# EEZ_DIB_PREL6_r1B3.net
KiCad netlist of a schematic drawn in EAGLE
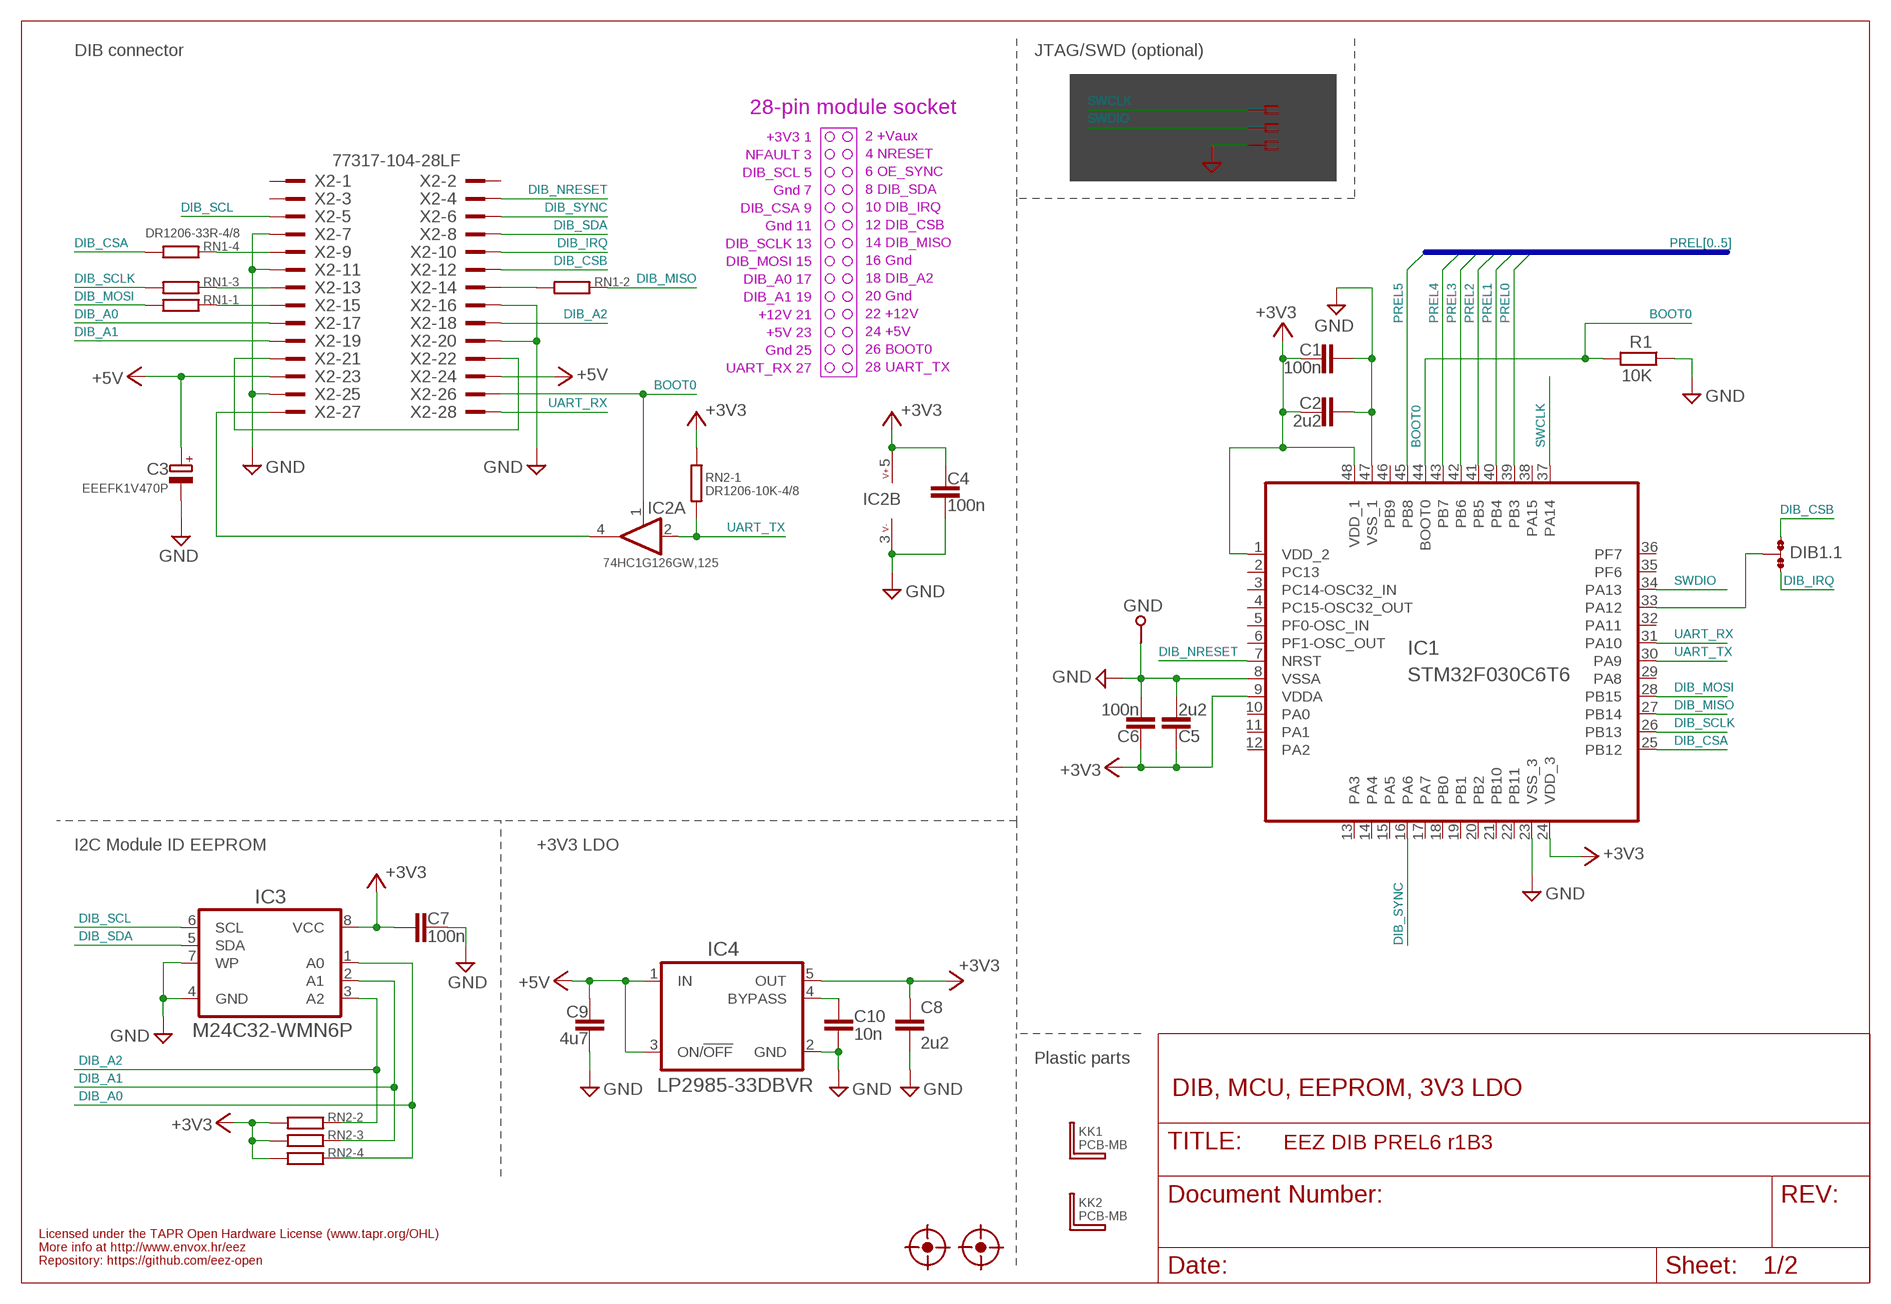
[diagram p0: schematic, sheet 1]
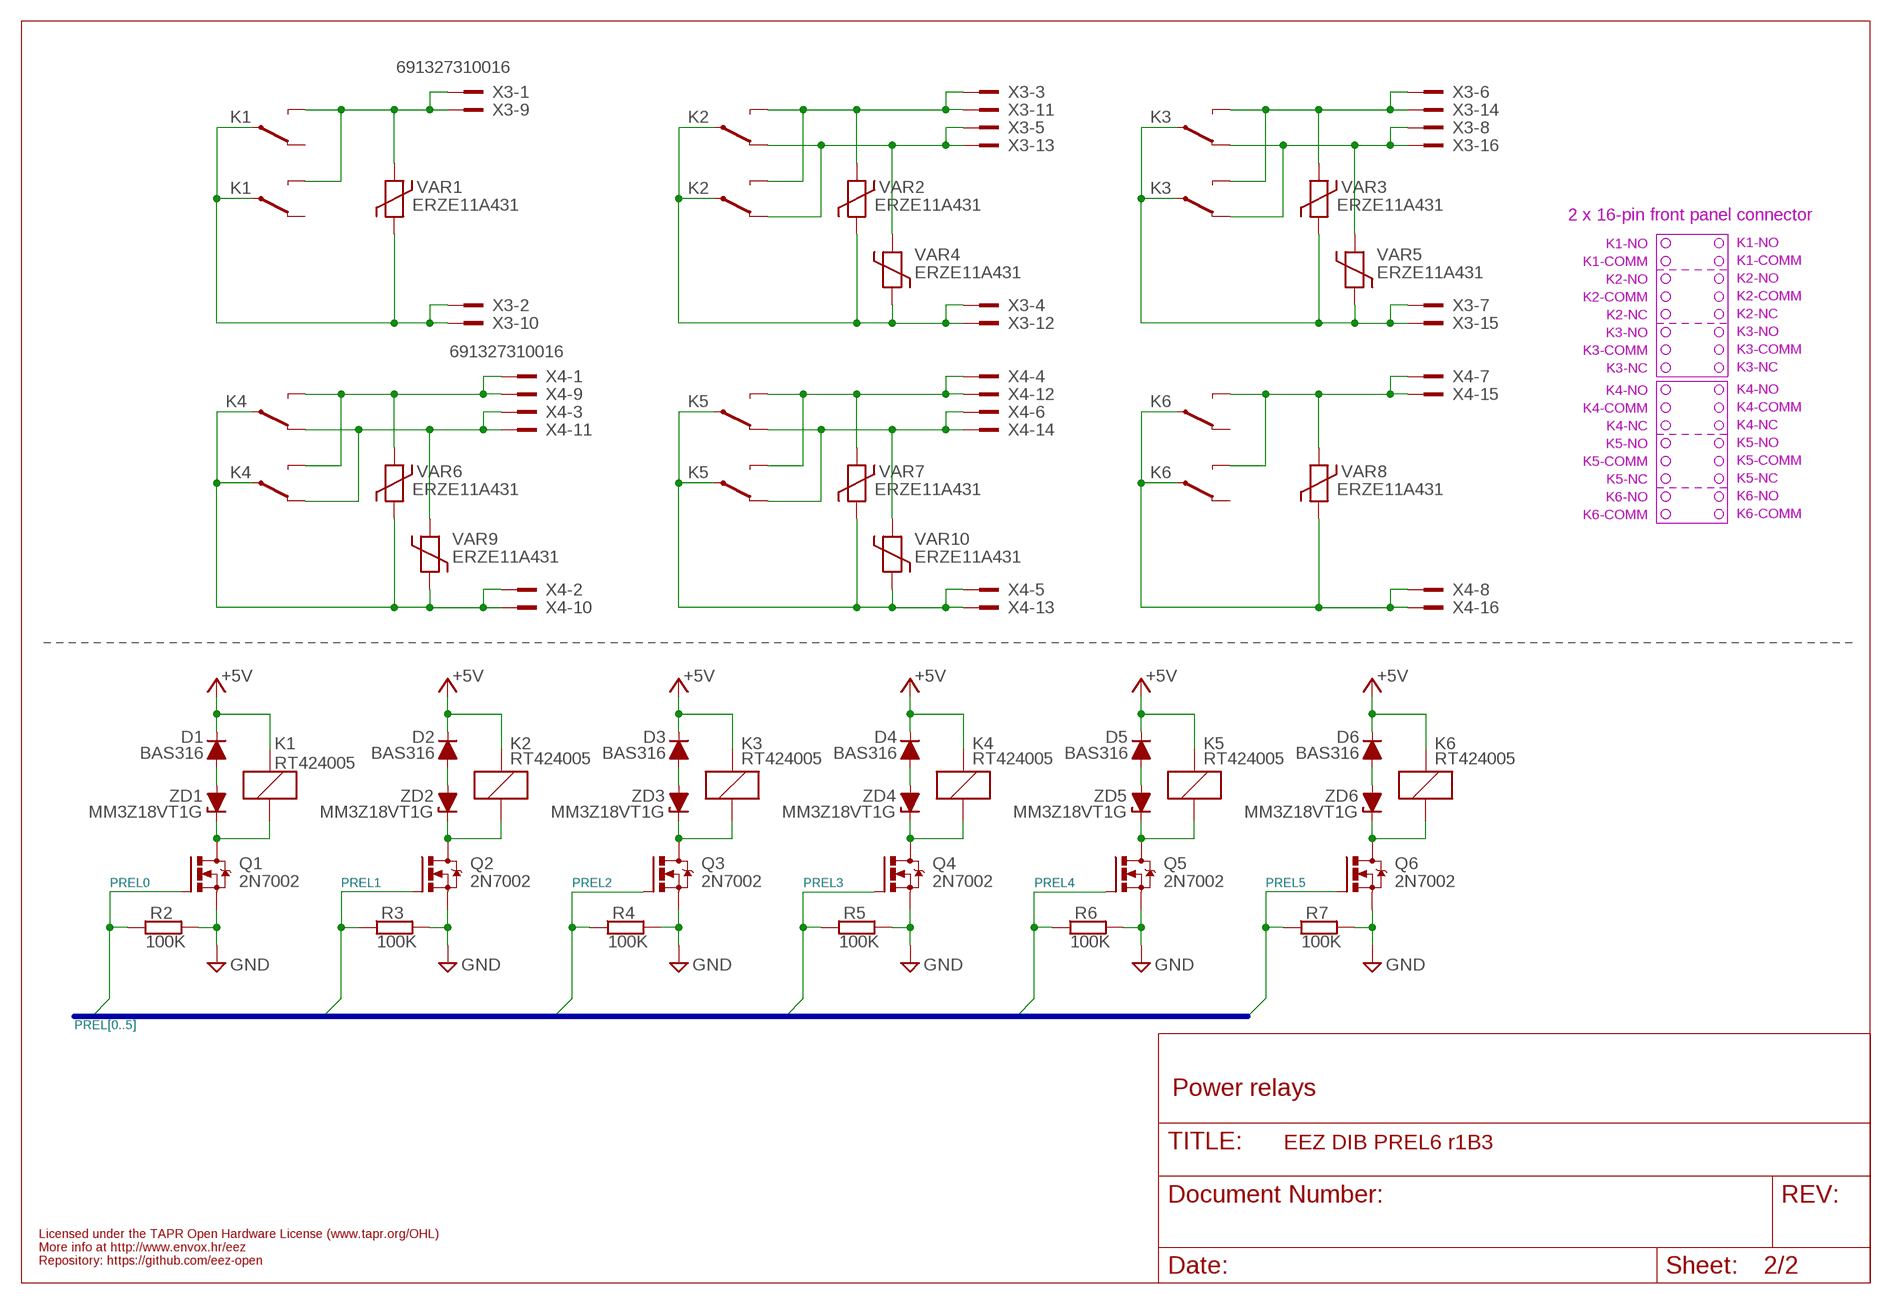
[diagram p1: schematic, sheet 2]

(export (version "E")
  (design (tool "Eeschema 10.0.6"))
  (components
    (comp (ref "D1")
      (value "BAS316")
      (footprint "eagle-import:SOD323-R")
      (libsource (lib "eagle-import") (part "DIODESOD323R"))
    )
    (comp (ref "D2")
      (value "BAS316")
      (footprint "eagle-import:SOD323-R")
      (libsource (lib "eagle-import") (part "DIODESOD323R"))
    )
    (comp (ref "D3")
      (value "BAS316")
      (footprint "eagle-import:SOD323-R")
      (libsource (lib "eagle-import") (part "DIODESOD323R"))
    )
    (comp (ref "D4")
      (value "BAS316")
      (footprint "eagle-import:SOD323-R")
      (libsource (lib "eagle-import") (part "DIODESOD323R"))
    )
    (comp (ref "D5")
      (value "BAS316")
      (footprint "eagle-import:SOD323-R")
      (libsource (lib "eagle-import") (part "DIODESOD323R"))
    )
    (comp (ref "D6")
      (value "BAS316")
      (footprint "eagle-import:SOD323-R")
      (libsource (lib "eagle-import") (part "DIODESOD323R"))
    )
    (comp (ref "K1")
      (value "RT424005")
      (footprint "eagle-import:RT-C_016A5_ROUND")
      (libsource (lib "eagle-import") (part "RELAY_RT314012-2"))
    )
    (comp (ref "K2")
      (value "RT424005")
      (footprint "eagle-import:RT-C_016A5_ROUND")
      (libsource (lib "eagle-import") (part "RELAY_RT314012-2"))
    )
    (comp (ref "K3")
      (value "RT424005")
      (footprint "eagle-import:RT-C_016A5_ROUND")
      (libsource (lib "eagle-import") (part "RELAY_RT314012-2"))
    )
    (comp (ref "K4")
      (value "RT424005")
      (footprint "eagle-import:RT-C_016A5_ROUND")
      (libsource (lib "eagle-import") (part "RELAY_RT314012-2"))
    )
    (comp (ref "K5")
      (value "RT424005")
      (footprint "eagle-import:RT-C_016A5_ROUND")
      (libsource (lib "eagle-import") (part "RELAY_RT314012-2"))
    )
    (comp (ref "K6")
      (value "RT424005")
      (footprint "eagle-import:RT-C_016A5_ROUND")
      (libsource (lib "eagle-import") (part "RELAY_RT314012-2"))
    )
    (comp (ref "Q1")
      (value "2N7002")
      (footprint "eagle-import:SOT103P240X110-3N")
      (fields
        (field (name "MPN") "2N7002-7-F")
        (field (name "MPN_1") "2N7002-7-F")
        (field (name "OC_FARNELL") "1713823")
        (field (name "OC_NEWARK") "25R5679")
        (field (name "PACKAGE") "SOT-23-3")
        (field (name "SUPPLIER") "DIODES INC.")
      )
      (libsource (lib "eagle-import") (part "2N7002"))
    )
    (comp (ref "Q2")
      (value "2N7002")
      (footprint "eagle-import:SOT103P240X110-3N")
      (fields
        (field (name "MPN") "2N7002-7-F")
        (field (name "MPN_1") "2N7002-7-F")
        (field (name "OC_FARNELL") "1713823")
        (field (name "OC_NEWARK") "25R5679")
        (field (name "PACKAGE") "SOT-23-3")
        (field (name "SUPPLIER") "DIODES INC.")
      )
      (libsource (lib "eagle-import") (part "2N7002"))
    )
    (comp (ref "Q3")
      (value "2N7002")
      (footprint "eagle-import:SOT103P240X110-3N")
      (fields
        (field (name "MPN") "2N7002-7-F")
        (field (name "MPN_1") "2N7002-7-F")
        (field (name "OC_FARNELL") "1713823")
        (field (name "OC_NEWARK") "25R5679")
        (field (name "PACKAGE") "SOT-23-3")
        (field (name "SUPPLIER") "DIODES INC.")
      )
      (libsource (lib "eagle-import") (part "2N7002"))
    )
    (comp (ref "Q4")
      (value "2N7002")
      (footprint "eagle-import:SOT103P240X110-3N")
      (fields
        (field (name "MPN") "2N7002-7-F")
        (field (name "MPN_1") "2N7002-7-F")
        (field (name "OC_FARNELL") "1713823")
        (field (name "OC_NEWARK") "25R5679")
        (field (name "PACKAGE") "SOT-23-3")
        (field (name "SUPPLIER") "DIODES INC.")
      )
      (libsource (lib "eagle-import") (part "2N7002"))
    )
    (comp (ref "Q5")
      (value "2N7002")
      (footprint "eagle-import:SOT103P240X110-3N")
      (fields
        (field (name "MPN") "2N7002-7-F")
        (field (name "MPN_1") "2N7002-7-F")
        (field (name "OC_FARNELL") "1713823")
        (field (name "OC_NEWARK") "25R5679")
        (field (name "PACKAGE") "SOT-23-3")
        (field (name "SUPPLIER") "DIODES INC.")
      )
      (libsource (lib "eagle-import") (part "2N7002"))
    )
    (comp (ref "Q6")
      (value "2N7002")
      (footprint "eagle-import:SOT103P240X110-3N")
      (fields
        (field (name "MPN") "2N7002-7-F")
        (field (name "MPN_1") "2N7002-7-F")
        (field (name "OC_FARNELL") "1713823")
        (field (name "OC_NEWARK") "25R5679")
        (field (name "PACKAGE") "SOT-23-3")
        (field (name "SUPPLIER") "DIODES INC.")
      )
      (libsource (lib "eagle-import") (part "2N7002"))
    )
    (comp (ref "R2")
      (value "100K")
      (footprint "eagle-import:R0805")
      (libsource (lib "eagle-import") (part "R-EU_R0805"))
    )
    (comp (ref "R3")
      (value "100K")
      (footprint "eagle-import:R0805")
      (libsource (lib "eagle-import") (part "R-EU_R0805"))
    )
    (comp (ref "R4")
      (value "100K")
      (footprint "eagle-import:R0805")
      (libsource (lib "eagle-import") (part "R-EU_R0805"))
    )
    (comp (ref "R5")
      (value "100K")
      (footprint "eagle-import:R0805")
      (libsource (lib "eagle-import") (part "R-EU_R0805"))
    )
    (comp (ref "R6")
      (value "100K")
      (footprint "eagle-import:R0805")
      (libsource (lib "eagle-import") (part "R-EU_R0805"))
    )
    (comp (ref "R7")
      (value "100K")
      (footprint "eagle-import:R0805")
      (libsource (lib "eagle-import") (part "R-EU_R0805"))
    )
    (comp (ref "VAR1")
      (value "ERZE11A431")
      (footprint "eagle-import:VARISTOR_13MM")
      (libsource (lib "eagle-import") (part "VARISTOR-13"))
    )
    (comp (ref "VAR2")
      (value "ERZE11A431")
      (footprint "eagle-import:VARISTOR_13MM")
      (libsource (lib "eagle-import") (part "VARISTOR-13"))
    )
    (comp (ref "VAR3")
      (value "ERZE11A431")
      (footprint "eagle-import:VARISTOR_13MM")
      (libsource (lib "eagle-import") (part "VARISTOR-13"))
    )
    (comp (ref "VAR4")
      (value "ERZE11A431")
      (footprint "eagle-import:VARISTOR_13MM")
      (libsource (lib "eagle-import") (part "VARISTOR-13"))
    )
    (comp (ref "VAR5")
      (value "ERZE11A431")
      (footprint "eagle-import:VARISTOR_13MM")
      (libsource (lib "eagle-import") (part "VARISTOR-13"))
    )
    (comp (ref "VAR6")
      (value "ERZE11A431")
      (footprint "eagle-import:VARISTOR_13MM")
      (libsource (lib "eagle-import") (part "VARISTOR-13"))
    )
    (comp (ref "VAR7")
      (value "ERZE11A431")
      (footprint "eagle-import:VARISTOR_13MM")
      (libsource (lib "eagle-import") (part "VARISTOR-13"))
    )
    (comp (ref "VAR8")
      (value "ERZE11A431")
      (footprint "eagle-import:VARISTOR_13MM")
      (libsource (lib "eagle-import") (part "VARISTOR-13"))
    )
    (comp (ref "VAR9")
      (value "ERZE11A431")
      (footprint "eagle-import:VARISTOR_13MM")
      (libsource (lib "eagle-import") (part "VARISTOR-13"))
    )
    (comp (ref "VAR10")
      (value "ERZE11A431")
      (footprint "eagle-import:VARISTOR_13MM")
      (libsource (lib "eagle-import") (part "VARISTOR-13"))
    )
    (comp (ref "X3")
      (value "691327310016")
      (footprint "eagle-import:691327310016")
      (libsource (lib "eagle-import") (part "691327310016"))
    )
    (comp (ref "X4")
      (value "691327310016")
      (footprint "eagle-import:691327310016")
      (libsource (lib "eagle-import") (part "691327310016"))
    )
    (comp (ref "ZD1")
      (value "MM3Z18VT1G")
      (footprint "eagle-import:SOD323-R")
      (libsource (lib "eagle-import") (part "ZENER-DIODESOD323R"))
    )
    (comp (ref "ZD2")
      (value "MM3Z18VT1G")
      (footprint "eagle-import:SOD323-R")
      (libsource (lib "eagle-import") (part "ZENER-DIODESOD323R"))
    )
    (comp (ref "ZD3")
      (value "MM3Z18VT1G")
      (footprint "eagle-import:SOD323-R")
      (libsource (lib "eagle-import") (part "ZENER-DIODESOD323R"))
    )
    (comp (ref "ZD4")
      (value "MM3Z18VT1G")
      (footprint "eagle-import:SOD323-R")
      (libsource (lib "eagle-import") (part "ZENER-DIODESOD323R"))
    )
    (comp (ref "ZD5")
      (value "MM3Z18VT1G")
      (footprint "eagle-import:SOD323-R")
      (libsource (lib "eagle-import") (part "ZENER-DIODESOD323R"))
    )
    (comp (ref "ZD6")
      (value "MM3Z18VT1G")
      (footprint "eagle-import:SOD323-R")
      (libsource (lib "eagle-import") (part "ZENER-DIODESOD323R"))
    )
    (comp (ref "C1")
      (value "100n")
      (footprint "eagle-import:C0603")
      (libsource (lib "eagle-import") (part "C-EUC0603"))
    )
    (comp (ref "C2")
      (value "2u2")
      (footprint "eagle-import:C0805")
      (libsource (lib "eagle-import") (part "C-EUC0805"))
    )
    (comp (ref "C3")
      (value "EEEFK1V470P")
      (footprint "eagle-import:CAPAE660X610N")
      (libsource (lib "eagle-import") (part "ECAPPANASONIC_H"))
    )
    (comp (ref "C4")
      (value "100n")
      (footprint "eagle-import:C0603")
      (libsource (lib "eagle-import") (part "C-EUC0603"))
    )
    (comp (ref "C5")
      (value "2u2")
      (footprint "eagle-import:C0805")
      (libsource (lib "eagle-import") (part "C-EUC0805"))
    )
    (comp (ref "C6")
      (value "100n")
      (footprint "eagle-import:C0603")
      (libsource (lib "eagle-import") (part "C-EUC0603"))
    )
    (comp (ref "C7")
      (value "100n")
      (footprint "eagle-import:C0603")
      (libsource (lib "eagle-import") (part "C-EUC0603"))
    )
    (comp (ref "C8")
      (value "2u2")
      (footprint "eagle-import:C0805")
      (libsource (lib "eagle-import") (part "C-EUC0805"))
    )
    (comp (ref "C9")
      (value "4u7")
      (footprint "eagle-import:C0805")
      (libsource (lib "eagle-import") (part "C-EUC0805"))
    )
    (comp (ref "C10")
      (value "10n")
      (footprint "eagle-import:C0805")
      (libsource (lib "eagle-import") (part "C-EUC0805"))
    )
    (comp (ref "DIB1.1")
      (value "JP3-CUT-0805-ROTATED")
      (footprint "eagle-import:JP3-0805-CUT2")
      (libsource (lib "eagle-import") (part "JP3-CUT-0805-ROTATED"))
    )
    (comp (ref "FM1")
      (value "FIDUCIAL_2")
      (footprint "eagle-import:FIDUCIAL_DUAL")
      (libsource (lib "eagle-import") (part "FIDUCIAL_2"))
    )
    (comp (ref "FM2")
      (value "FIDUCIAL_2")
      (footprint "eagle-import:FIDUCIAL_DUAL")
      (libsource (lib "eagle-import") (part "FIDUCIAL_2"))
    )
    (comp (ref "GND")
      (value "PCB_TEST_TABSHIELD")
      (footprint "eagle-import:PCB_SHIELD_TAB")
      (libsource (lib "eagle-import") (part "PCB_TEST_TABSHIELD"))
    )
    (comp (ref "IC1")
      (value "STM32F030C6T6")
      (footprint "eagle-import:LQFP-48")
      (libsource (lib "eagle-import") (part "STM32F030C6T6"))
    )
    (comp (ref "IC2")
      (value "74HC1G126GW,125")
      (footprint "eagle-import:SOT65P210X110-5N")
      (libsource (lib "eagle-import") (part "74HC1G126GW,125"))
    )
    (comp (ref "IC3")
      (value "M24C32-WMN6P")
      (footprint "eagle-import:SOIC127P600X173-8N")
      (libsource (lib "eagle-import") (part "AT24CXXSOIC8"))
    )
    (comp (ref "IC4")
      (value "LP2985-33DBVR")
      (footprint "eagle-import:SOT95P270X145-5N")
      (libsource (lib "eagle-import") (part "LP2985"))
    )
    (comp (ref "KK1")
      (value "PCB-MB")
      (footprint "eagle-import:PCB-MB")
      (libsource (lib "eagle-import") (part "PCB-MB"))
    )
    (comp (ref "KK2")
      (value "PCB-MB")
      (footprint "eagle-import:PCB-MB")
      (libsource (lib "eagle-import") (part "PCB-MB"))
    )
    (comp (ref "R1")
      (value "10K")
      (footprint "eagle-import:R0805")
      (libsource (lib "eagle-import") (part "R-EU_R0805"))
    )
    (comp (ref "RN1")
      (value "DR1206-33R-4/8")
      (footprint "eagle-import:CAY16")
      (libsource (lib "eagle-import") (part "R_ARRAY4"))
    )
    (comp (ref "RN2")
      (value "DR1206-10K-4/8")
      (footprint "eagle-import:CAY16")
      (libsource (lib "eagle-import") (part "R_ARRAY4"))
    )
    (comp (ref "X1")
      (value "N.C.")
      (footprint "eagle-import:SSW-106-02-S-S")
      (fields (field (name "MPN") "SSW-106-02-S-S"))
      (libsource (lib "eagle-import") (part "SSW-106-02-S-S"))
    )
    (comp (ref "X2")
      (value "77317-104-28LF")
      (footprint "eagle-import:77317-104-28LF")
      (libsource (lib "eagle-import") (part "77317-104-28LF"))
    )
  )
  (nets
    (net (code "1") (name "+3V3") (class "Default")
      (node (ref "C1") (pin "2") (pinfunction "2_2") (pintype "passive"))
      (node (ref "C2") (pin "1") (pinfunction "1_1") (pintype "passive"))
      (node (ref "C4") (pin "1") (pinfunction "1_1") (pintype "passive"))
      (node (ref "C5") (pin "2") (pinfunction "2_2") (pintype "passive"))
      (node (ref "C6") (pin "1") (pinfunction "1_1") (pintype "passive"))
      (node (ref "C7") (pin "2") (pinfunction "2_2") (pintype "passive"))
      (node (ref "C8") (pin "1") (pinfunction "1_1") (pintype "passive"))
      (node (ref "IC1") (pin "1") (pinfunction "VDD_2_1") (pintype "passive"))
      (node (ref "IC1") (pin "24") (pinfunction "VDD_3_24") (pintype "passive"))
      (node (ref "IC1") (pin "48") (pinfunction "VDD_1_48") (pintype "passive"))
      (node (ref "IC1") (pin "9") (pinfunction "VDDA_9") (pintype "passive"))
      (node (ref "IC2") (pin "5") (pinfunction "V+_5") (pintype "power_in"))
      (node (ref "IC3") (pin "8") (pinfunction "VCC_8") (pintype "power_in"))
      (node (ref "IC4") (pin "5") (pinfunction "OUT_5") (pintype "passive"))
      (node (ref "RN2") (pin "5") (pinfunction "2_5") (pintype "passive"))
      (node (ref "RN2") (pin "6") (pinfunction "2_6") (pintype "passive"))
      (node (ref "RN2") (pin "7") (pinfunction "2_7") (pintype "passive"))
      (node (ref "RN2") (pin "8") (pinfunction "2_8") (pintype "passive"))
    )
    (net (code "2") (name "+5V") (class "Default")
      (node (ref "C3") (pin "1") (pinfunction "+_1") (pintype "passive"))
      (node (ref "C9") (pin "2") (pinfunction "2_2") (pintype "passive"))
      (node (ref "D1") (pin "C") (pinfunction "C_C") (pintype "passive"))
      (node (ref "D2") (pin "C") (pinfunction "C_C") (pintype "passive"))
      (node (ref "D3") (pin "C") (pinfunction "C_C") (pintype "passive"))
      (node (ref "D4") (pin "C") (pinfunction "C_C") (pintype "passive"))
      (node (ref "D5") (pin "C") (pinfunction "C_C") (pintype "passive"))
      (node (ref "D6") (pin "C") (pinfunction "C_C") (pintype "passive"))
      (node (ref "IC4") (pin "1") (pinfunction "IN_1") (pintype "input"))
      (node (ref "IC4") (pin "3") (pinfunction "ON/~{OFF}_3") (pintype "input"))
      (node (ref "K1") (pin "A2") (pinfunction "C1_A2") (pintype "passive"))
      (node (ref "K2") (pin "A2") (pinfunction "C1_A2") (pintype "passive"))
      (node (ref "K3") (pin "A2") (pinfunction "C1_A2") (pintype "passive"))
      (node (ref "K4") (pin "A2") (pinfunction "C1_A2") (pintype "passive"))
      (node (ref "K5") (pin "A2") (pinfunction "C1_A2") (pintype "passive"))
      (node (ref "K6") (pin "A2") (pinfunction "C1_A2") (pintype "passive"))
      (node (ref "X2") (pin "23") (pinfunction "1_23") (pintype "passive"))
      (node (ref "X2") (pin "24") (pinfunction "1_24") (pintype "passive"))
    )
    (net (code "5") (name "BOOT0") (class "Default")
      (node (ref "IC1") (pin "44") (pinfunction "BOOT0_44") (pintype "input"))
      (node (ref "IC2") (pin "1") (pinfunction "EN_1") (pintype "input"))
      (node (ref "R1") (pin "2") (pinfunction "2_2") (pintype "passive"))
      (node (ref "X2") (pin "26") (pinfunction "1_26") (pintype "passive"))
    )
    (net (code "6") (name "DIB_A0") (class "Default")
      (node (ref "IC3") (pin "1") (pinfunction "A0_1") (pintype "input"))
      (node (ref "RN2") (pin "4") (pinfunction "1_4") (pintype "passive"))
      (node (ref "X2") (pin "17") (pinfunction "1_17") (pintype "passive"))
    )
    (net (code "7") (name "DIB_A1") (class "Default")
      (node (ref "IC3") (pin "2") (pinfunction "A1_2") (pintype "input"))
      (node (ref "RN2") (pin "3") (pinfunction "1_3") (pintype "passive"))
      (node (ref "X2") (pin "19") (pinfunction "1_19") (pintype "passive"))
    )
    (net (code "8") (name "DIB_A2") (class "Default")
      (node (ref "IC3") (pin "3") (pinfunction "A2_3") (pintype "input"))
      (node (ref "RN2") (pin "2") (pinfunction "1_2") (pintype "passive"))
      (node (ref "X2") (pin "18") (pinfunction "1_18") (pintype "passive"))
    )
    (net (code "9") (name "DIB_CSA") (class "Default")
      (node (ref "IC1") (pin "25") (pinfunction "PB12_25") (pintype "bidirectional"))
      (node (ref "RN1") (pin "4") (pinfunction "1_4") (pintype "passive"))
    )
    (net (code "10") (name "DIB_CSB") (class "Default")
      (node (ref "DIB1.1") (pin "NO") (pinfunction "NO_NO") (pintype "passive"))
      (node (ref "X2") (pin "12") (pinfunction "1_12") (pintype "passive"))
    )
    (net (code "11") (name "DIB_IRQ") (class "Default")
      (node (ref "DIB1.1") (pin "NC") (pinfunction "NC_NC") (pintype "passive"))
      (node (ref "X2") (pin "10") (pinfunction "1_10") (pintype "passive"))
    )
    (net (code "12") (name "DIB_MISO") (class "Default")
      (node (ref "IC1") (pin "27") (pinfunction "PB14_27") (pintype "bidirectional"))
      (node (ref "RN1") (pin "2") (pinfunction "1_2") (pintype "passive"))
    )
    (net (code "13") (name "DIB_MOSI") (class "Default")
      (node (ref "IC1") (pin "28") (pinfunction "PB15_28") (pintype "bidirectional"))
      (node (ref "RN1") (pin "1") (pinfunction "1_1") (pintype "passive"))
    )
    (net (code "14") (name "DIB_NRESET") (class "Default")
      (node (ref "IC1") (pin "7") (pinfunction "NRST_7") (pintype "input"))
      (node (ref "X2") (pin "4") (pinfunction "1_4") (pintype "passive"))
    )
    (net (code "15") (name "DIB_SCL") (class "Default")
      (node (ref "IC3") (pin "6") (pinfunction "SCL_6") (pintype "bidirectional"))
      (node (ref "X2") (pin "5") (pinfunction "1_5") (pintype "passive"))
    )
    (net (code "16") (name "DIB_SCLK") (class "Default")
      (node (ref "IC1") (pin "26") (pinfunction "PB13_26") (pintype "bidirectional"))
      (node (ref "RN1") (pin "3") (pinfunction "1_3") (pintype "passive"))
    )
    (net (code "17") (name "DIB_SDA") (class "Default")
      (node (ref "IC3") (pin "5") (pinfunction "SDA_5") (pintype "bidirectional"))
      (node (ref "X2") (pin "8") (pinfunction "1_8") (pintype "passive"))
    )
    (net (code "18") (name "DIB_SYNC") (class "Default")
      (node (ref "IC1") (pin "16") (pinfunction "PA6_16") (pintype "bidirectional"))
      (node (ref "X2") (pin "6") (pinfunction "1_6") (pintype "passive"))
    )
    (net (code "19") (name "GND") (class "Default")
      (node (ref "C1") (pin "1") (pinfunction "1_1") (pintype "passive"))
      (node (ref "C10") (pin "1") (pinfunction "1_1") (pintype "passive"))
      (node (ref "C2") (pin "2") (pinfunction "2_2") (pintype "passive"))
      (node (ref "C3") (pin "2") (pinfunction "-_2") (pintype "passive"))
      (node (ref "C4") (pin "2") (pinfunction "2_2") (pintype "passive"))
      (node (ref "C5") (pin "1") (pinfunction "1_1") (pintype "passive"))
      (node (ref "C6") (pin "2") (pinfunction "2_2") (pintype "passive"))
      (node (ref "C7") (pin "1") (pinfunction "1_1") (pintype "passive"))
      (node (ref "C8") (pin "2") (pinfunction "2_2") (pintype "passive"))
      (node (ref "C9") (pin "1") (pinfunction "1_1") (pintype "passive"))
      (node (ref "GND") (pin "1") (pinfunction "P$1_1") (pintype "bidirectional"))
      (node (ref "IC1") (pin "23") (pinfunction "VSS_3_23") (pintype "passive"))
      (node (ref "IC1") (pin "47") (pinfunction "VSS_1_47") (pintype "passive"))
      (node (ref "IC1") (pin "8") (pinfunction "VSSA_8") (pintype "passive"))
      (node (ref "IC2") (pin "3") (pinfunction "V-_3") (pintype "power_in"))
      (node (ref "IC3") (pin "4") (pinfunction "GND_4") (pintype "passive"))
      (node (ref "IC3") (pin "7") (pinfunction "WP_7") (pintype "input"))
      (node (ref "IC4") (pin "2") (pinfunction "GND_2") (pintype "passive"))
      (node (ref "Q1") (pin "2") (pinfunction "S_2") (pintype "passive"))
      (node (ref "Q2") (pin "2") (pinfunction "S_2") (pintype "passive"))
      (node (ref "Q3") (pin "2") (pinfunction "S_2") (pintype "passive"))
      (node (ref "Q4") (pin "2") (pinfunction "S_2") (pintype "passive"))
      (node (ref "Q5") (pin "2") (pinfunction "S_2") (pintype "passive"))
      (node (ref "Q6") (pin "2") (pinfunction "S_2") (pintype "passive"))
      (node (ref "R1") (pin "1") (pinfunction "1_1") (pintype "passive"))
      (node (ref "R2") (pin "2") (pinfunction "2_2") (pintype "passive"))
      (node (ref "R3") (pin "2") (pinfunction "2_2") (pintype "passive"))
      (node (ref "R4") (pin "2") (pinfunction "2_2") (pintype "passive"))
      (node (ref "R5") (pin "2") (pinfunction "2_2") (pintype "passive"))
      (node (ref "R6") (pin "2") (pinfunction "2_2") (pintype "passive"))
      (node (ref "R7") (pin "2") (pinfunction "2_2") (pintype "passive"))
      (node (ref "X1") (pin "3") (pinfunction "1_3") (pintype "passive"))
      (node (ref "X2") (pin "11") (pinfunction "1_11") (pintype "passive"))
      (node (ref "X2") (pin "16") (pinfunction "1_16") (pintype "passive"))
      (node (ref "X2") (pin "20") (pinfunction "1_20") (pintype "passive"))
      (node (ref "X2") (pin "25") (pinfunction "1_25") (pintype "passive"))
      (node (ref "X2") (pin "7") (pinfunction "1_7") (pintype "passive"))
    )
    (net (code "20") (name "Net-(D1-PadA)") (class "Default")
      (node (ref "D1") (pin "A") (pinfunction "A_A") (pintype "passive"))
      (node (ref "ZD1") (pin "A") (pinfunction "A_A") (pintype "passive"))
    )
    (net (code "21") (name "Net-(D2-PadA)") (class "Default")
      (node (ref "D2") (pin "A") (pinfunction "A_A") (pintype "passive"))
      (node (ref "ZD2") (pin "A") (pinfunction "A_A") (pintype "passive"))
    )
    (net (code "22") (name "Net-(D3-PadA)") (class "Default")
      (node (ref "D3") (pin "A") (pinfunction "A_A") (pintype "passive"))
      (node (ref "ZD3") (pin "A") (pinfunction "A_A") (pintype "passive"))
    )
    (net (code "23") (name "Net-(D4-PadA)") (class "Default")
      (node (ref "D4") (pin "A") (pinfunction "A_A") (pintype "passive"))
      (node (ref "ZD4") (pin "A") (pinfunction "A_A") (pintype "passive"))
    )
    (net (code "24") (name "Net-(D5-PadA)") (class "Default")
      (node (ref "D5") (pin "A") (pinfunction "A_A") (pintype "passive"))
      (node (ref "ZD5") (pin "A") (pinfunction "A_A") (pintype "passive"))
    )
    (net (code "25") (name "Net-(D6-PadA)") (class "Default")
      (node (ref "D6") (pin "A") (pinfunction "A_A") (pintype "passive"))
      (node (ref "ZD6") (pin "A") (pinfunction "A_A") (pintype "passive"))
    )
    (net (code "26") (name "Net-(IC1-PA12)") (class "Default")
      (node (ref "DIB1.1") (pin "COM") (pinfunction "COM_COM") (pintype "passive"))
      (node (ref "IC1") (pin "33") (pinfunction "PA12_33") (pintype "bidirectional"))
    )
    (net (code "27") (name "Net-(IC2A-O)") (class "Default")
      (node (ref "IC2") (pin "4") (pinfunction "O_4") (pintype "output"))
      (node (ref "X2") (pin "27") (pinfunction "1_27") (pintype "passive"))
    )
    (net (code "28") (name "Net-(IC4-BYPASS)") (class "Default")
      (node (ref "C10") (pin "2") (pinfunction "2_2") (pintype "passive"))
      (node (ref "IC4") (pin "4") (pinfunction "BYPASS_4") (pintype "passive"))
    )
    (net (code "29") (name "Net-(K1A-O)") (class "Default")
      (node (ref "K1") (pin "14A") (pinfunction "O_14A") (pintype "passive"))
      (node (ref "K1") (pin "14B") (pinfunction "O_14B") (pintype "passive"))
      (node (ref "VAR1") (pin "2") (pinfunction "P$2_2") (pintype "bidirectional"))
      (node (ref "X3") (pin "1") (pinfunction "1_1") (pintype "passive"))
      (node (ref "X3") (pin "9") (pinfunction "1_9") (pintype "passive"))
    )
    (net (code "30") (name "Net-(K1A-P)") (class "Default")
      (node (ref "K1") (pin "11A") (pinfunction "P_11A") (pintype "passive"))
      (node (ref "K1") (pin "11B") (pinfunction "P_11B") (pintype "passive"))
      (node (ref "VAR1") (pin "1") (pinfunction "P$1_1") (pintype "bidirectional"))
      (node (ref "X3") (pin "10") (pinfunction "1_10") (pintype "passive"))
      (node (ref "X3") (pin "2") (pinfunction "1_2") (pintype "passive"))
    )
    (net (code "31") (name "Net-(K1C-C2)") (class "Default")
      (node (ref "K1") (pin "A1") (pinfunction "C2_A1") (pintype "passive"))
      (node (ref "Q1") (pin "3") (pinfunction "D_3") (pintype "passive"))
      (node (ref "ZD1") (pin "C") (pinfunction "C_C") (pintype "passive"))
    )
    (net (code "32") (name "Net-(K2A-O)") (class "Default")
      (node (ref "K2") (pin "14A") (pinfunction "O_14A") (pintype "passive"))
      (node (ref "K2") (pin "14B") (pinfunction "O_14B") (pintype "passive"))
      (node (ref "VAR2") (pin "2") (pinfunction "P$2_2") (pintype "bidirectional"))
      (node (ref "X3") (pin "11") (pinfunction "1_11") (pintype "passive"))
      (node (ref "X3") (pin "3") (pinfunction "1_3") (pintype "passive"))
    )
    (net (code "33") (name "Net-(K2A-P)") (class "Default")
      (node (ref "K2") (pin "11A") (pinfunction "P_11A") (pintype "passive"))
      (node (ref "K2") (pin "11B") (pinfunction "P_11B") (pintype "passive"))
      (node (ref "VAR2") (pin "1") (pinfunction "P$1_1") (pintype "bidirectional"))
      (node (ref "VAR4") (pin "1") (pinfunction "P$1_1") (pintype "bidirectional"))
      (node (ref "X3") (pin "12") (pinfunction "1_12") (pintype "passive"))
      (node (ref "X3") (pin "4") (pinfunction "1_4") (pintype "passive"))
    )
    (net (code "34") (name "Net-(K2A-S)") (class "Default")
      (node (ref "K2") (pin "12A") (pinfunction "S_12A") (pintype "passive"))
      (node (ref "K2") (pin "12B") (pinfunction "S_12B") (pintype "passive"))
      (node (ref "VAR4") (pin "2") (pinfunction "P$2_2") (pintype "bidirectional"))
      (node (ref "X3") (pin "13") (pinfunction "1_13") (pintype "passive"))
      (node (ref "X3") (pin "5") (pinfunction "1_5") (pintype "passive"))
    )
    (net (code "35") (name "Net-(K2C-C2)") (class "Default")
      (node (ref "K2") (pin "A1") (pinfunction "C2_A1") (pintype "passive"))
      (node (ref "Q2") (pin "3") (pinfunction "D_3") (pintype "passive"))
      (node (ref "ZD2") (pin "C") (pinfunction "C_C") (pintype "passive"))
    )
    (net (code "36") (name "Net-(K3A-O)") (class "Default")
      (node (ref "K3") (pin "14A") (pinfunction "O_14A") (pintype "passive"))
      (node (ref "K3") (pin "14B") (pinfunction "O_14B") (pintype "passive"))
      (node (ref "VAR3") (pin "2") (pinfunction "P$2_2") (pintype "bidirectional"))
      (node (ref "X3") (pin "14") (pinfunction "1_14") (pintype "passive"))
      (node (ref "X3") (pin "6") (pinfunction "1_6") (pintype "passive"))
    )
    (net (code "37") (name "Net-(K3A-P)") (class "Default")
      (node (ref "K3") (pin "11A") (pinfunction "P_11A") (pintype "passive"))
      (node (ref "K3") (pin "11B") (pinfunction "P_11B") (pintype "passive"))
      (node (ref "VAR3") (pin "1") (pinfunction "P$1_1") (pintype "bidirectional"))
      (node (ref "VAR5") (pin "1") (pinfunction "P$1_1") (pintype "bidirectional"))
      (node (ref "X3") (pin "15") (pinfunction "1_15") (pintype "passive"))
      (node (ref "X3") (pin "7") (pinfunction "1_7") (pintype "passive"))
    )
    (net (code "38") (name "Net-(K3A-S)") (class "Default")
      (node (ref "K3") (pin "12A") (pinfunction "S_12A") (pintype "passive"))
      (node (ref "K3") (pin "12B") (pinfunction "S_12B") (pintype "passive"))
      (node (ref "VAR5") (pin "2") (pinfunction "P$2_2") (pintype "bidirectional"))
      (node (ref "X3") (pin "16") (pinfunction "1_16") (pintype "passive"))
      (node (ref "X3") (pin "8") (pinfunction "1_8") (pintype "passive"))
    )
    (net (code "39") (name "Net-(K3C-C2)") (class "Default")
      (node (ref "K3") (pin "A1") (pinfunction "C2_A1") (pintype "passive"))
      (node (ref "Q3") (pin "3") (pinfunction "D_3") (pintype "passive"))
      (node (ref "ZD3") (pin "C") (pinfunction "C_C") (pintype "passive"))
    )
    (net (code "40") (name "Net-(K4A-O)") (class "Default")
      (node (ref "K4") (pin "14A") (pinfunction "O_14A") (pintype "passive"))
      (node (ref "K4") (pin "14B") (pinfunction "O_14B") (pintype "passive"))
      (node (ref "VAR6") (pin "2") (pinfunction "P$2_2") (pintype "bidirectional"))
      (node (ref "X4") (pin "1") (pinfunction "1_1") (pintype "passive"))
      (node (ref "X4") (pin "9") (pinfunction "1_9") (pintype "passive"))
    )
    (net (code "41") (name "Net-(K4A-P)") (class "Default")
      (node (ref "K4") (pin "11A") (pinfunction "P_11A") (pintype "passive"))
      (node (ref "K4") (pin "11B") (pinfunction "P_11B") (pintype "passive"))
      (node (ref "VAR6") (pin "1") (pinfunction "P$1_1") (pintype "bidirectional"))
      (node (ref "VAR9") (pin "1") (pinfunction "P$1_1") (pintype "bidirectional"))
      (node (ref "X4") (pin "10") (pinfunction "1_10") (pintype "passive"))
      (node (ref "X4") (pin "2") (pinfunction "1_2") (pintype "passive"))
    )
    (net (code "42") (name "Net-(K4A-S)") (class "Default")
      (node (ref "K4") (pin "12A") (pinfunction "S_12A") (pintype "passive"))
      (node (ref "K4") (pin "12B") (pinfunction "S_12B") (pintype "passive"))
      (node (ref "VAR9") (pin "2") (pinfunction "P$2_2") (pintype "bidirectional"))
      (node (ref "X4") (pin "11") (pinfunction "1_11") (pintype "passive"))
      (node (ref "X4") (pin "3") (pinfunction "1_3") (pintype "passive"))
    )
    (net (code "43") (name "Net-(K4C-C2)") (class "Default")
      (node (ref "K4") (pin "A1") (pinfunction "C2_A1") (pintype "passive"))
      (node (ref "Q4") (pin "3") (pinfunction "D_3") (pintype "passive"))
      (node (ref "ZD4") (pin "C") (pinfunction "C_C") (pintype "passive"))
    )
    (net (code "44") (name "Net-(K5A-O)") (class "Default")
      (node (ref "K5") (pin "14A") (pinfunction "O_14A") (pintype "passive"))
      (node (ref "K5") (pin "14B") (pinfunction "O_14B") (pintype "passive"))
      (node (ref "VAR7") (pin "2") (pinfunction "P$2_2") (pintype "bidirectional"))
      (node (ref "X4") (pin "12") (pinfunction "1_12") (pintype "passive"))
      (node (ref "X4") (pin "4") (pinfunction "1_4") (pintype "passive"))
    )
    (net (code "45") (name "Net-(K5A-P)") (class "Default")
      (node (ref "K5") (pin "11A") (pinfunction "P_11A") (pintype "passive"))
      (node (ref "K5") (pin "11B") (pinfunction "P_11B") (pintype "passive"))
      (node (ref "VAR10") (pin "1") (pinfunction "P$1_1") (pintype "bidirectional"))
      (node (ref "VAR7") (pin "1") (pinfunction "P$1_1") (pintype "bidirectional"))
      (node (ref "X4") (pin "13") (pinfunction "1_13") (pintype "passive"))
      (node (ref "X4") (pin "5") (pinfunction "1_5") (pintype "passive"))
    )
    (net (code "46") (name "Net-(K5A-S)") (class "Default")
      (node (ref "K5") (pin "12A") (pinfunction "S_12A") (pintype "passive"))
      (node (ref "K5") (pin "12B") (pinfunction "S_12B") (pintype "passive"))
      (node (ref "VAR10") (pin "2") (pinfunction "P$2_2") (pintype "bidirectional"))
      (node (ref "X4") (pin "14") (pinfunction "1_14") (pintype "passive"))
      (node (ref "X4") (pin "6") (pinfunction "1_6") (pintype "passive"))
    )
    (net (code "47") (name "Net-(K5C-C2)") (class "Default")
      (node (ref "K5") (pin "A1") (pinfunction "C2_A1") (pintype "passive"))
      (node (ref "Q5") (pin "3") (pinfunction "D_3") (pintype "passive"))
      (node (ref "ZD5") (pin "C") (pinfunction "C_C") (pintype "passive"))
    )
    (net (code "48") (name "Net-(K6A-O)") (class "Default")
      (node (ref "K6") (pin "14A") (pinfunction "O_14A") (pintype "passive"))
      (node (ref "K6") (pin "14B") (pinfunction "O_14B") (pintype "passive"))
      (node (ref "VAR8") (pin "2") (pinfunction "P$2_2") (pintype "bidirectional"))
      (node (ref "X4") (pin "15") (pinfunction "1_15") (pintype "passive"))
      (node (ref "X4") (pin "7") (pinfunction "1_7") (pintype "passive"))
    )
    (net (code "49") (name "Net-(K6A-P)") (class "Default")
      (node (ref "K6") (pin "11A") (pinfunction "P_11A") (pintype "passive"))
      (node (ref "K6") (pin "11B") (pinfunction "P_11B") (pintype "passive"))
      (node (ref "VAR8") (pin "1") (pinfunction "P$1_1") (pintype "bidirectional"))
      (node (ref "X4") (pin "16") (pinfunction "1_16") (pintype "passive"))
      (node (ref "X4") (pin "8") (pinfunction "1_8") (pintype "passive"))
    )
    (net (code "50") (name "Net-(K6C-C2)") (class "Default")
      (node (ref "K6") (pin "A1") (pinfunction "C2_A1") (pintype "passive"))
      (node (ref "Q6") (pin "3") (pinfunction "D_3") (pintype "passive"))
      (node (ref "ZD6") (pin "C") (pinfunction "C_C") (pintype "passive"))
    )
    (net (code "51") (name "Net-(RN1A-2)") (class "Default")
      (node (ref "RN1") (pin "8") (pinfunction "2_8") (pintype "passive"))
      (node (ref "X2") (pin "15") (pinfunction "1_15") (pintype "passive"))
    )
    (net (code "52") (name "Net-(RN1B-2)") (class "Default")
      (node (ref "RN1") (pin "7") (pinfunction "2_7") (pintype "passive"))
      (node (ref "X2") (pin "14") (pinfunction "1_14") (pintype "passive"))
    )
    (net (code "53") (name "Net-(RN1C-2)") (class "Default")
      (node (ref "RN1") (pin "6") (pinfunction "2_6") (pintype "passive"))
      (node (ref "X2") (pin "13") (pinfunction "1_13") (pintype "passive"))
    )
    (net (code "54") (name "Net-(RN1D-2)") (class "Default")
      (node (ref "RN1") (pin "5") (pinfunction "2_5") (pintype "passive"))
      (node (ref "X2") (pin "9") (pinfunction "1_9") (pintype "passive"))
    )
    (net (code "55") (name "Net-(X2N-1)") (class "Default")
      (node (ref "X2") (pin "21") (pinfunction "1_21") (pintype "passive"))
      (node (ref "X2") (pin "22") (pinfunction "1_22") (pintype "passive"))
    )
    (net (code "56") (name "PREL0") (class "Default")
      (node (ref "IC1") (pin "39") (pinfunction "PB3_39") (pintype "bidirectional"))
      (node (ref "Q1") (pin "1") (pinfunction "G_1") (pintype "passive"))
      (node (ref "R2") (pin "1") (pinfunction "1_1") (pintype "passive"))
    )
    (net (code "57") (name "PREL1") (class "Default")
      (node (ref "IC1") (pin "40") (pinfunction "PB4_40") (pintype "bidirectional"))
      (node (ref "Q2") (pin "1") (pinfunction "G_1") (pintype "passive"))
      (node (ref "R3") (pin "1") (pinfunction "1_1") (pintype "passive"))
    )
    (net (code "58") (name "PREL2") (class "Default")
      (node (ref "IC1") (pin "41") (pinfunction "PB5_41") (pintype "bidirectional"))
      (node (ref "Q3") (pin "1") (pinfunction "G_1") (pintype "passive"))
      (node (ref "R4") (pin "1") (pinfunction "1_1") (pintype "passive"))
    )
    (net (code "59") (name "PREL3") (class "Default")
      (node (ref "IC1") (pin "42") (pinfunction "PB6_42") (pintype "bidirectional"))
      (node (ref "Q4") (pin "1") (pinfunction "G_1") (pintype "passive"))
      (node (ref "R5") (pin "1") (pinfunction "1_1") (pintype "passive"))
    )
    (net (code "60") (name "PREL4") (class "Default")
      (node (ref "IC1") (pin "43") (pinfunction "PB7_43") (pintype "bidirectional"))
      (node (ref "Q5") (pin "1") (pinfunction "G_1") (pintype "passive"))
      (node (ref "R6") (pin "1") (pinfunction "1_1") (pintype "passive"))
    )
    (net (code "61") (name "PREL5") (class "Default")
      (node (ref "IC1") (pin "45") (pinfunction "PB8_45") (pintype "bidirectional"))
      (node (ref "Q6") (pin "1") (pinfunction "G_1") (pintype "passive"))
      (node (ref "R7") (pin "1") (pinfunction "1_1") (pintype "passive"))
    )
    (net (code "62") (name "SWCLK") (class "Default")
      (node (ref "IC1") (pin "37") (pinfunction "PA14_37") (pintype "bidirectional"))
      (node (ref "X1") (pin "2") (pinfunction "1_2") (pintype "passive"))
    )
    (net (code "63") (name "SWDIO") (class "Default")
      (node (ref "IC1") (pin "34") (pinfunction "PA13_34") (pintype "bidirectional"))
      (node (ref "X1") (pin "4") (pinfunction "1_4") (pintype "passive"))
    )
    (net (code "64") (name "UART_RX") (class "Default")
      (node (ref "IC1") (pin "31") (pinfunction "PA10_31") (pintype "bidirectional"))
      (node (ref "X2") (pin "28") (pinfunction "1_28") (pintype "passive"))
    )
    (net (code "65") (name "UART_TX") (class "Default")
      (node (ref "IC1") (pin "30") (pinfunction "PA9_30") (pintype "bidirectional"))
      (node (ref "IC2") (pin "2") (pinfunction "I_2") (pintype "input"))
      (node (ref "RN2") (pin "1") (pinfunction "1_1") (pintype "passive"))
    )
    (net (code "66") (name "unconnected-(IC1-PA0-Pad10)") (class "Default")
      (node (ref "IC1") (pin "10") (pinfunction "PA0_10") (pintype "bidirectional"))
    )
    (net (code "67") (name "unconnected-(IC1-PA1-Pad11)") (class "Default")
      (node (ref "IC1") (pin "11") (pinfunction "PA1_11") (pintype "bidirectional"))
    )
    (net (code "68") (name "unconnected-(IC1-PA2-Pad12)") (class "Default")
      (node (ref "IC1") (pin "12") (pinfunction "PA2_12") (pintype "bidirectional"))
    )
    (net (code "69") (name "unconnected-(IC1-PA3-Pad13)") (class "Default")
      (node (ref "IC1") (pin "13") (pinfunction "PA3_13") (pintype "bidirectional"))
    )
    (net (code "70") (name "unconnected-(IC1-PA4-Pad14)") (class "Default")
      (node (ref "IC1") (pin "14") (pinfunction "PA4_14") (pintype "bidirectional"))
    )
    (net (code "71") (name "unconnected-(IC1-PA5-Pad15)") (class "Default")
      (node (ref "IC1") (pin "15") (pinfunction "PA5_15") (pintype "bidirectional"))
    )
    (net (code "72") (name "unconnected-(IC1-PA7-Pad17)") (class "Default")
      (node (ref "IC1") (pin "17") (pinfunction "PA7_17") (pintype "bidirectional"))
    )
    (net (code "73") (name "unconnected-(IC1-PA8-Pad29)") (class "Default")
      (node (ref "IC1") (pin "29") (pinfunction "PA8_29") (pintype "bidirectional"))
    )
    (net (code "74") (name "unconnected-(IC1-PA11-Pad32)") (class "Default")
      (node (ref "IC1") (pin "32") (pinfunction "PA11_32") (pintype "bidirectional"))
    )
    (net (code "75") (name "unconnected-(IC1-PA15-Pad38)") (class "Default")
      (node (ref "IC1") (pin "38") (pinfunction "PA15_38") (pintype "bidirectional"))
    )
    (net (code "76") (name "unconnected-(IC1-PB0-Pad18)") (class "Default")
      (node (ref "IC1") (pin "18") (pinfunction "PB0_18") (pintype "bidirectional"))
    )
    (net (code "77") (name "unconnected-(IC1-PB1-Pad19)") (class "Default")
      (node (ref "IC1") (pin "19") (pinfunction "PB1_19") (pintype "bidirectional"))
    )
    (net (code "78") (name "unconnected-(IC1-PB2-Pad20)") (class "Default")
      (node (ref "IC1") (pin "20") (pinfunction "PB2_20") (pintype "bidirectional"))
    )
    (net (code "79") (name "unconnected-(IC1-PB9-Pad46)") (class "Default")
      (node (ref "IC1") (pin "46") (pinfunction "PB9_46") (pintype "bidirectional"))
    )
    (net (code "80") (name "unconnected-(IC1-PB10-Pad21)") (class "Default")
      (node (ref "IC1") (pin "21") (pinfunction "PB10_21") (pintype "bidirectional"))
    )
    (net (code "81") (name "unconnected-(IC1-PB11-Pad22)") (class "Default")
      (node (ref "IC1") (pin "22") (pinfunction "PB11_22") (pintype "bidirectional"))
    )
    (net (code "82") (name "unconnected-(IC1-PC13-Pad2)") (class "Default")
      (node (ref "IC1") (pin "2") (pinfunction "PC13_2") (pintype "bidirectional"))
    )
    (net (code "83") (name "unconnected-(IC1-PC14-OSC32_IN-Pad3)") (class "Default")
      (node (ref "IC1") (pin "3") (pinfunction "PC14-OSC32_IN_3") (pintype "bidirectional"))
    )
    (net (code "84") (name "unconnected-(IC1-PC15-OSC32_OUT-Pad4)") (class "Default")
      (node (ref "IC1") (pin "4") (pinfunction "PC15-OSC32_OUT_4") (pintype "bidirectional"))
    )
    (net (code "85") (name "unconnected-(IC1-PF0-OSC_IN-Pad5)") (class "Default")
      (node (ref "IC1") (pin "5") (pinfunction "PF0-OSC_IN_5") (pintype "bidirectional"))
    )
    (net (code "86") (name "unconnected-(IC1-PF1-OSC_OUT-Pad6)") (class "Default")
      (node (ref "IC1") (pin "6") (pinfunction "PF1-OSC_OUT_6") (pintype "bidirectional"))
    )
    (net (code "87") (name "unconnected-(IC1-PF6-Pad35)") (class "Default")
      (node (ref "IC1") (pin "35") (pinfunction "PF6_35") (pintype "bidirectional"))
    )
    (net (code "88") (name "unconnected-(IC1-PF7-Pad36)") (class "Default")
      (node (ref "IC1") (pin "36") (pinfunction "PF7_36") (pintype "bidirectional"))
    )
    (net (code "89") (name "unconnected-(K1A-S-Pad12A)") (class "Default")
      (node (ref "K1") (pin "12A") (pinfunction "S_12A") (pintype "passive"))
    )
    (net (code "90") (name "unconnected-(K1B-S-Pad12B)") (class "Default")
      (node (ref "K1") (pin "12B") (pinfunction "S_12B") (pintype "passive"))
    )
    (net (code "91") (name "unconnected-(K6A-S-Pad12A)") (class "Default")
      (node (ref "K6") (pin "12A") (pinfunction "S_12A") (pintype "passive"))
    )
    (net (code "92") (name "unconnected-(K6B-S-Pad12B)") (class "Default")
      (node (ref "K6") (pin "12B") (pinfunction "S_12B") (pintype "passive"))
    )
    (net (code "93") (name "unconnected-(X2-Pad1)") (class "Default")
      (node (ref "X2") (pin "1") (pinfunction "1_1") (pintype "passive"))
    )
    (net (code "94") (name "unconnected-(X2L-1-Pad2)") (class "Default")
      (node (ref "X2") (pin "2") (pinfunction "1_2") (pintype "passive"))
    )
    (net (code "95") (name "unconnected-(X2V-1-Pad3)") (class "Default")
      (node (ref "X2") (pin "3") (pinfunction "1_3") (pintype "passive"))
    )
  )
)
